# kidstimer.net
KiCad netlist of a schematic drawn in EAGLE
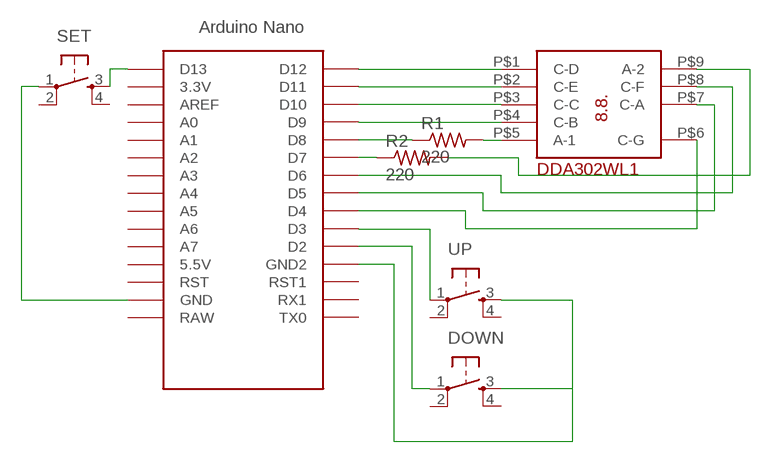
[diagram p0: schematic, sheet 1]

(export (version "E")
  (design (tool "Eeschema 10.0.6"))
  (components
    (comp (ref "DOWN")
      (value "TAC_SWITCHPTH")
      (footprint "eagle-import:TACTILE-PTH")
      (libsource (lib "eagle-import") (part "TAC_SWITCHPTH"))
    )
    (comp (ref "R1")
      (value "220")
      (footprint "eagle-import:0207_10")
      (libsource (lib "eagle-import") (part "R-US_0207/10"))
    )
    (comp (ref "R2")
      (value "220")
      (footprint "eagle-import:0207_10")
      (libsource (lib "eagle-import") (part "R-US_0207/10"))
    )
    (comp (ref "SET")
      (value "TAC_SWITCHPTH")
      (footprint "eagle-import:TACTILE-PTH")
      (libsource (lib "eagle-import") (part "TAC_SWITCHPTH"))
    )
    (comp (ref "U$1")
      (value "DDA302WL1DIP9")
      (footprint "eagle-import:DIP9")
      (libsource (lib "eagle-import") (part "DDA302WL1DIP9"))
    )
    (comp (ref "U$2")
      (value "NANO")
      (footprint "eagle-import:NANO")
      (libsource (lib "eagle-import") (part "NANO"))
    )
    (comp (ref "UP")
      (value "TAC_SWITCHPTH")
      (footprint "eagle-import:TACTILE-PTH")
      (libsource (lib "eagle-import") (part "TAC_SWITCHPTH"))
    )
  )
  (nets
    (net (code "1") (name "Net-(DOWN-Pad1)") (class "Default")
      (node (ref "DOWN") (pin "1") (pinfunction "1_1") (pintype "passive"))
      (node (ref "U$2") (pin "D2") (pinfunction "D2_D2") (pintype "bidirectional"))
    )
    (net (code "2") (name "Net-(R1-Pad1)") (class "Default")
      (node (ref "R1") (pin "1") (pinfunction "1_1") (pintype "passive"))
      (node (ref "U$2") (pin "D8") (pinfunction "D8_D8") (pintype "bidirectional"))
    )
    (net (code "3") (name "Net-(R2-Pad1)") (class "Default")
      (node (ref "R2") (pin "1") (pinfunction "1_1") (pintype "passive"))
      (node (ref "U$2") (pin "D7") (pinfunction "D7_D7") (pintype "bidirectional"))
    )
    (net (code "4") (name "Net-(SET-Pad1)") (class "Default")
      (node (ref "SET") (pin "1") (pinfunction "1_1") (pintype "passive"))
      (node (ref "U$2") (pin "GND") (pinfunction "GND_GND") (pintype "bidirectional"))
    )
    (net (code "5") (name "Net-(SET-Pad3)") (class "Default")
      (node (ref "SET") (pin "3") (pinfunction "3_3") (pintype "passive"))
      (node (ref "U$2") (pin "D13") (pinfunction "D13_D13") (pintype "bidirectional"))
    )
    (net (code "6") (name "Net-(U$1-A-1)") (class "Default")
      (node (ref "R1") (pin "2") (pinfunction "2_2") (pintype "passive"))
      (node (ref "U$1") (pin "P$5") (pinfunction "A-1_P$5") (pintype "bidirectional"))
    )
    (net (code "7") (name "Net-(U$1-A-2)") (class "Default")
      (node (ref "R2") (pin "2") (pinfunction "2_2") (pintype "passive"))
      (node (ref "U$1") (pin "P$9") (pinfunction "A-2_P$9") (pintype "bidirectional"))
    )
    (net (code "8") (name "Net-(U$1-C-A)") (class "Default")
      (node (ref "U$1") (pin "P$7") (pinfunction "C-A_P$7") (pintype "bidirectional"))
      (node (ref "U$2") (pin "D5") (pinfunction "D5_D5") (pintype "bidirectional"))
    )
    (net (code "9") (name "Net-(U$1-C-B)") (class "Default")
      (node (ref "U$1") (pin "P$4") (pinfunction "C-B_P$4") (pintype "bidirectional"))
      (node (ref "U$2") (pin "D9") (pinfunction "D9_D9") (pintype "bidirectional"))
    )
    (net (code "10") (name "Net-(U$1-C-C)") (class "Default")
      (node (ref "U$1") (pin "P$3") (pinfunction "C-C_P$3") (pintype "bidirectional"))
      (node (ref "U$2") (pin "D10") (pinfunction "D10_D10") (pintype "bidirectional"))
    )
    (net (code "11") (name "Net-(U$1-C-D)") (class "Default")
      (node (ref "U$1") (pin "P$1") (pinfunction "C-D_P$1") (pintype "bidirectional"))
      (node (ref "U$2") (pin "D12") (pinfunction "D12_D12") (pintype "bidirectional"))
    )
    (net (code "12") (name "Net-(U$1-C-E)") (class "Default")
      (node (ref "U$1") (pin "P$2") (pinfunction "C-E_P$2") (pintype "bidirectional"))
      (node (ref "U$2") (pin "D11") (pinfunction "D11_D11") (pintype "bidirectional"))
    )
    (net (code "13") (name "Net-(U$1-C-F)") (class "Default")
      (node (ref "U$1") (pin "P$8") (pinfunction "C-F_P$8") (pintype "bidirectional"))
      (node (ref "U$2") (pin "D6") (pinfunction "D6_D6") (pintype "bidirectional"))
    )
    (net (code "14") (name "Net-(U$1-C-G)") (class "Default")
      (node (ref "U$1") (pin "P$6") (pinfunction "C-G_P$6") (pintype "bidirectional"))
      (node (ref "U$2") (pin "D4") (pinfunction "D4_D4") (pintype "bidirectional"))
    )
    (net (code "15") (name "Net-(U$2-GND2)") (class "Default")
      (node (ref "DOWN") (pin "3") (pinfunction "3_3") (pintype "passive"))
      (node (ref "U$2") (pin "GND1") (pinfunction "GND2_GND1") (pintype "bidirectional"))
      (node (ref "UP") (pin "3") (pinfunction "3_3") (pintype "passive"))
    )
    (net (code "16") (name "Net-(U$2-PadD3)") (class "Default")
      (node (ref "U$2") (pin "D3") (pinfunction "D3_D3") (pintype "bidirectional"))
      (node (ref "UP") (pin "1") (pinfunction "1_1") (pintype "passive"))
    )
    (net (code "17") (name "unconnected-(DOWN-Pad2)") (class "Default")
      (node (ref "DOWN") (pin "2") (pinfunction "2_2") (pintype "passive"))
    )
    (net (code "18") (name "unconnected-(DOWN-Pad4)") (class "Default")
      (node (ref "DOWN") (pin "4") (pinfunction "4_4") (pintype "passive"))
    )
    (net (code "19") (name "unconnected-(SET-Pad2)") (class "Default")
      (node (ref "SET") (pin "2") (pinfunction "2_2") (pintype "passive"))
    )
    (net (code "20") (name "unconnected-(SET-Pad4)") (class "Default")
      (node (ref "SET") (pin "4") (pinfunction "4_4") (pintype "passive"))
    )
    (net (code "21") (name "unconnected-(U$2-5.5V-Pad5V)") (class "Default")
      (node (ref "U$2") (pin "5V") (pinfunction "5.5V_5V") (pintype "bidirectional"))
    )
    (net (code "22") (name "unconnected-(U$2-Pad3.3V)") (class "Default")
      (node (ref "U$2") (pin "3.3V") (pinfunction "3.3V_3.3V") (pintype "bidirectional"))
    )
    (net (code "23") (name "unconnected-(U$2-PadA0)") (class "Default")
      (node (ref "U$2") (pin "A0") (pinfunction "A0_A0") (pintype "bidirectional"))
    )
    (net (code "24") (name "unconnected-(U$2-PadA1)") (class "Default")
      (node (ref "U$2") (pin "A1") (pinfunction "A1_A1") (pintype "bidirectional"))
    )
    (net (code "25") (name "unconnected-(U$2-PadA2)") (class "Default")
      (node (ref "U$2") (pin "A2") (pinfunction "A2_A2") (pintype "bidirectional"))
    )
    (net (code "26") (name "unconnected-(U$2-PadA3)") (class "Default")
      (node (ref "U$2") (pin "A3") (pinfunction "A3_A3") (pintype "bidirectional"))
    )
    (net (code "27") (name "unconnected-(U$2-PadA4)") (class "Default")
      (node (ref "U$2") (pin "A4") (pinfunction "A4_A4") (pintype "bidirectional"))
    )
    (net (code "28") (name "unconnected-(U$2-PadA5)") (class "Default")
      (node (ref "U$2") (pin "A5") (pinfunction "A5_A5") (pintype "bidirectional"))
    )
    (net (code "29") (name "unconnected-(U$2-PadA6)") (class "Default")
      (node (ref "U$2") (pin "A6") (pinfunction "A6_A6") (pintype "bidirectional"))
    )
    (net (code "30") (name "unconnected-(U$2-PadA7)") (class "Default")
      (node (ref "U$2") (pin "A7") (pinfunction "A7_A7") (pintype "bidirectional"))
    )
    (net (code "31") (name "unconnected-(U$2-PadAREF)") (class "Default")
      (node (ref "U$2") (pin "AREF") (pinfunction "AREF_AREF") (pintype "bidirectional"))
    )
    (net (code "32") (name "unconnected-(U$2-PadICSP1)") (class "Default")
      (node (ref "U$2") (pin "ICSP1") (pinfunction "ICSP1_ICSP1") (pintype "bidirectional"))
    )
    (net (code "33") (name "unconnected-(U$2-PadICSP2)") (class "Default")
      (node (ref "U$2") (pin "ICSP2") (pinfunction "ICSP2_ICSP2") (pintype "bidirectional"))
    )
    (net (code "34") (name "unconnected-(U$2-PadICSP3)") (class "Default")
      (node (ref "U$2") (pin "ICSP3") (pinfunction "ICSP3_ICSP3") (pintype "bidirectional"))
    )
    (net (code "35") (name "unconnected-(U$2-PadICSP4)") (class "Default")
      (node (ref "U$2") (pin "ICSP4") (pinfunction "ICSP4_ICSP4") (pintype "bidirectional"))
    )
    (net (code "36") (name "unconnected-(U$2-PadICSP5)") (class "Default")
      (node (ref "U$2") (pin "ICSP5") (pinfunction "ICSP5_ICSP5") (pintype "bidirectional"))
    )
    (net (code "37") (name "unconnected-(U$2-PadICSP6)") (class "Default")
      (node (ref "U$2") (pin "ICSP6") (pinfunction "ICSP6_ICSP6") (pintype "bidirectional"))
    )
    (net (code "38") (name "unconnected-(U$2-PadRAW)") (class "Default")
      (node (ref "U$2") (pin "RAW") (pinfunction "RAW_RAW") (pintype "bidirectional"))
    )
    (net (code "39") (name "unconnected-(U$2-PadRST)") (class "Default")
      (node (ref "U$2") (pin "RST") (pinfunction "RST_RST") (pintype "bidirectional"))
    )
    (net (code "40") (name "unconnected-(U$2-PadRST1)") (class "Default")
      (node (ref "U$2") (pin "RST1") (pinfunction "RST1_RST1") (pintype "bidirectional"))
    )
    (net (code "41") (name "unconnected-(U$2-PadRX1)") (class "Default")
      (node (ref "U$2") (pin "RX1") (pinfunction "RX1_RX1") (pintype "bidirectional"))
    )
    (net (code "42") (name "unconnected-(U$2-PadTX0)") (class "Default")
      (node (ref "U$2") (pin "TX0") (pinfunction "TX0_TX0") (pintype "bidirectional"))
    )
    (net (code "43") (name "unconnected-(UP-Pad2)") (class "Default")
      (node (ref "UP") (pin "2") (pinfunction "2_2") (pintype "passive"))
    )
    (net (code "44") (name "unconnected-(UP-Pad4)") (class "Default")
      (node (ref "UP") (pin "4") (pinfunction "4_4") (pintype "passive"))
    )
  )
)
